# TD1-V2.net
KiCad netlist of a schematic drawn in EAGLE
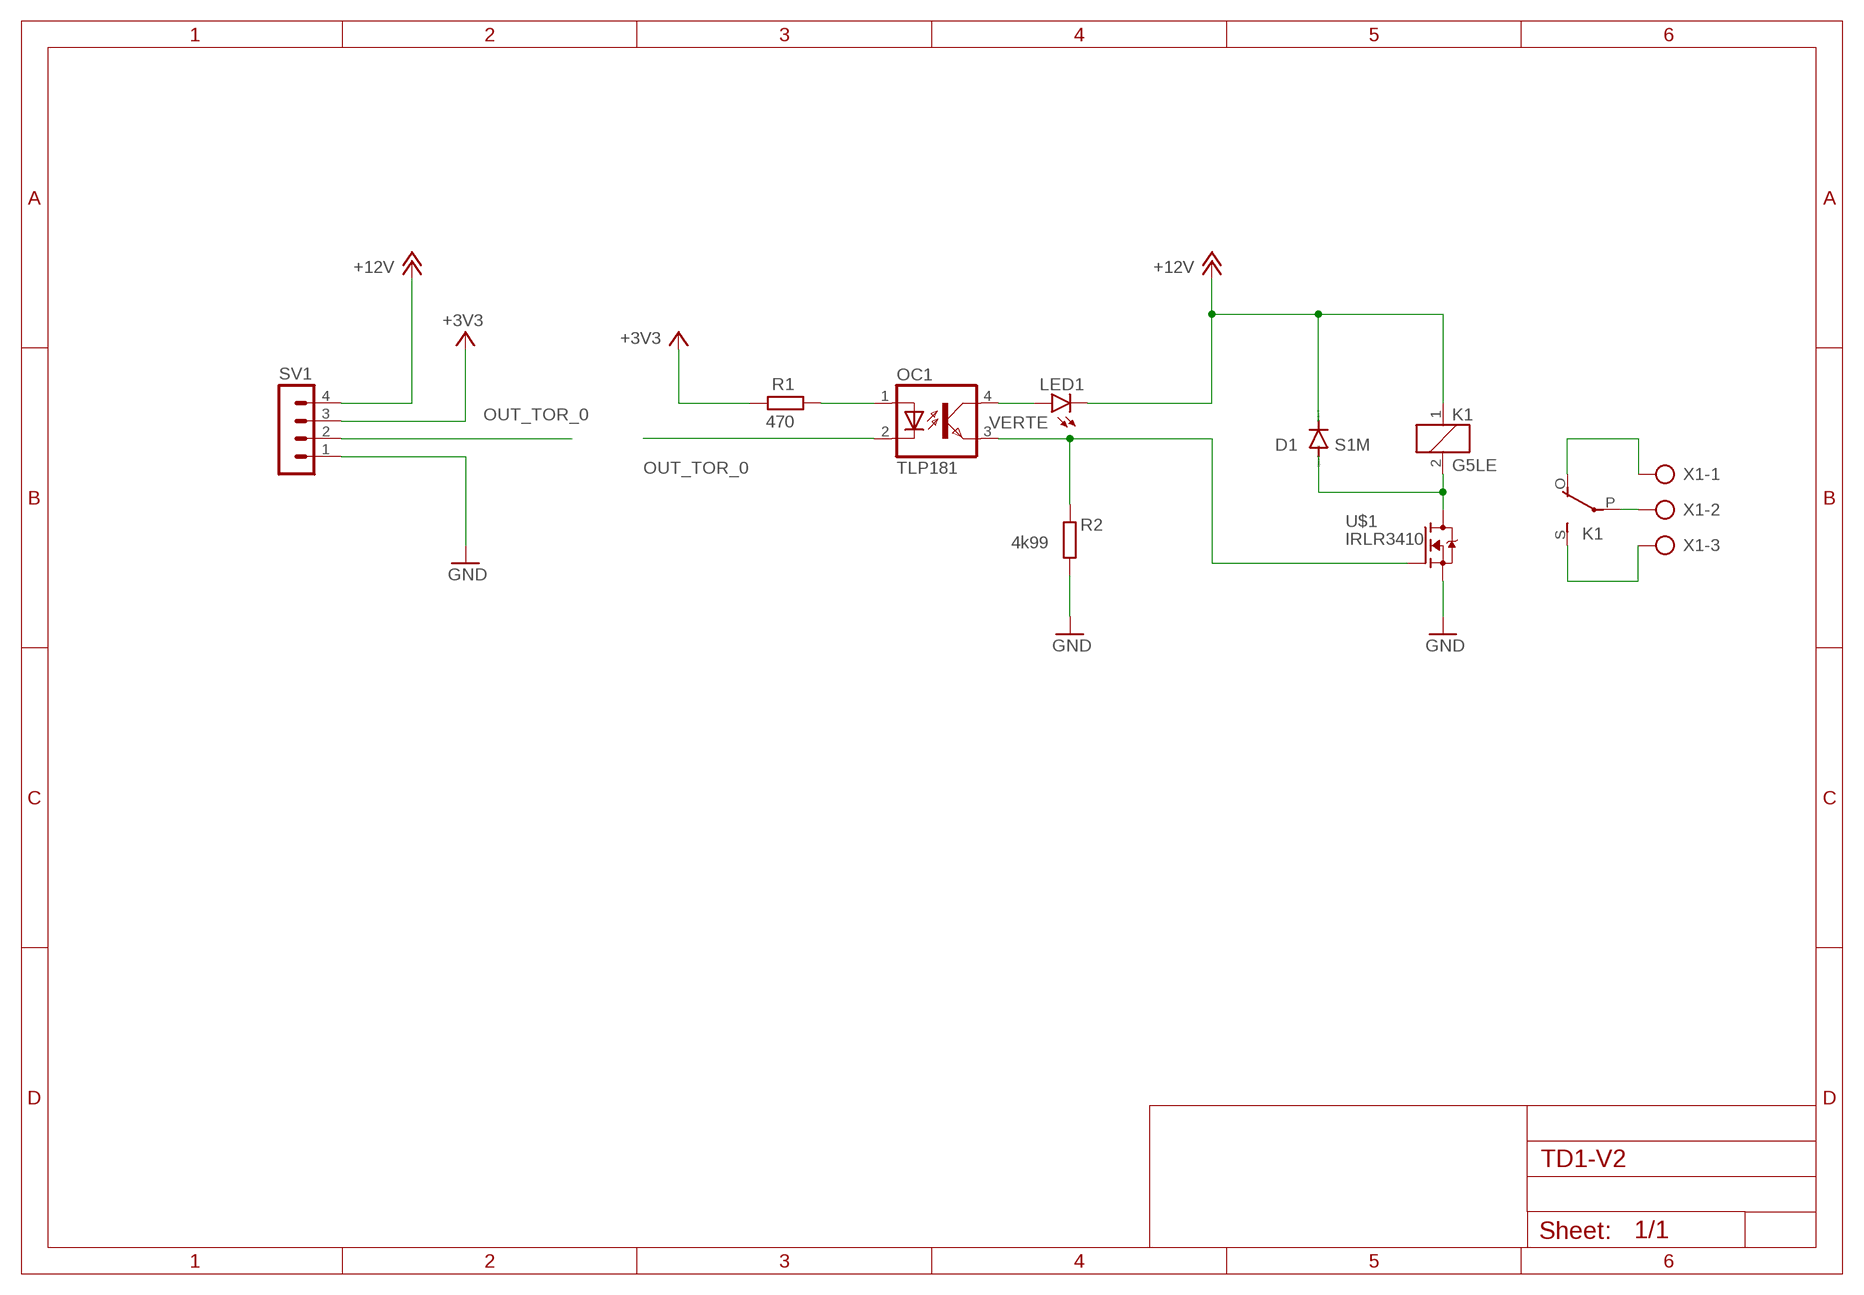
[diagram p0: schematic, sheet 1]

(export (version "E")
  (design (tool "Eeschema 10.0.6"))
  (components
    (comp (ref "D1")
      (value "S1M")
      (footprint "eagle-import:SMA")
      (libsource (lib "eagle-import") (part "S1M"))
    )
    (comp (ref "K1")
      (value "G5LE")
      (footprint "eagle-import:G5LE")
      (libsource (lib "eagle-import") (part "G5LE"))
    )
    (comp (ref "LED1")
      (value "VERTE")
      (footprint "eagle-import:LED5MM")
      (libsource (lib "eagle-import") (part "LED5MM"))
    )
    (comp (ref "OC1")
      (value "TLP181")
      (footprint "eagle-import:SO-4")
      (libsource (lib "eagle-import") (part "TLP181"))
    )
    (comp (ref "R1")
      (value "470")
      (footprint "eagle-import:0204_7")
      (libsource (lib "eagle-import") (part "R-EU_0204/7"))
    )
    (comp (ref "R2")
      (value "4k99")
      (footprint "eagle-import:0204_7")
      (libsource (lib "eagle-import") (part "R-EU_0204/7"))
    )
    (comp (ref "SV1")
      (value "MA04-1")
      (footprint "eagle-import:MA04-1")
      (libsource (lib "eagle-import") (part "MA04-1"))
    )
    (comp (ref "U$1")
      (value "IRLR3410")
      (footprint "eagle-import:TO252")
      (libsource (lib "eagle-import") (part "IRLR3410"))
    )
    (comp (ref "X1")
      (value "AK300/3")
      (footprint "eagle-import:AK300_3")
      (libsource (lib "eagle-import") (part "AK300/3"))
    )
  )
  (nets
    (net (code "1") (name "+3V3") (class "Default")
      (node (ref "R1") (pin "2") (pinfunction "2_2") (pintype "passive"))
      (node (ref "SV1") (pin "3") (pinfunction "3_3") (pintype "passive"))
    )
    (net (code "2") (name "+12V") (class "Default")
      (node (ref "D1") (pin "C") (pinfunction "C_C") (pintype "passive"))
      (node (ref "K1") (pin "1") (pinfunction "1_1") (pintype "passive"))
      (node (ref "LED1") (pin "K") (pinfunction "C_K") (pintype "passive"))
      (node (ref "SV1") (pin "4") (pinfunction "4_4") (pintype "passive"))
    )
    (net (code "3") (name "/OUT_TOR_0") (class "Default")
      (node (ref "OC1") (pin "2") (pinfunction "C_2") (pintype "passive"))
      (node (ref "SV1") (pin "2") (pinfunction "2_2") (pintype "passive"))
    )
    (net (code "4") (name "GND") (class "Default")
      (node (ref "R2") (pin "2") (pinfunction "2_2") (pintype "passive"))
      (node (ref "SV1") (pin "1") (pinfunction "1_1") (pintype "passive"))
      (node (ref "U$1") (pin "3") (pinfunction "S_3") (pintype "passive"))
    )
    (net (code "5") (name "Net-(OC1-A)") (class "Default")
      (node (ref "OC1") (pin "1") (pinfunction "A_1") (pintype "passive"))
      (node (ref "R1") (pin "1") (pinfunction "1_1") (pintype "passive"))
    )
    (net (code "6") (name "Net-(OC1-COL)") (class "Default")
      (node (ref "LED1") (pin "A") (pinfunction "A_A") (pintype "passive"))
      (node (ref "OC1") (pin "4") (pinfunction "COL_4") (pintype "passive"))
    )
    (net (code "7") (name "Net-(OC1-EMIT)") (class "Default")
      (node (ref "OC1") (pin "3") (pinfunction "EMIT_3") (pintype "passive"))
      (node (ref "R2") (pin "1") (pinfunction "1_1") (pintype "passive"))
      (node (ref "U$1") (pin "1") (pinfunction "G_1") (pintype "passive"))
    )
    (net (code "8") (name "Net-(U$1-D)") (class "Default")
      (node (ref "D1") (pin "A") (pinfunction "A_A") (pintype "passive"))
      (node (ref "K1") (pin "2") (pinfunction "2_2") (pintype "passive"))
      (node (ref "U$1") (pin "4") (pinfunction "D_4") (pintype "passive"))
    )
    (net (code "9") (name "Net-(X1A-KL)") (class "Default")
      (node (ref "K1") (pin "O") (pinfunction "O_O") (pintype "passive"))
      (node (ref "X1") (pin "1") (pinfunction "KL_1") (pintype "passive"))
    )
    (net (code "10") (name "Net-(X1B-KL)") (class "Default")
      (node (ref "K1") (pin "P") (pinfunction "P_P") (pintype "passive"))
      (node (ref "X1") (pin "2") (pinfunction "KL_2") (pintype "passive"))
    )
    (net (code "11") (name "Net-(X1C-KL)") (class "Default")
      (node (ref "K1") (pin "S") (pinfunction "S_S") (pintype "passive"))
      (node (ref "X1") (pin "3") (pinfunction "KL_3") (pintype "passive"))
    )
  )
)
